# Project.net
KiCad netlist of a schematic drawn in EasyEDA Pro
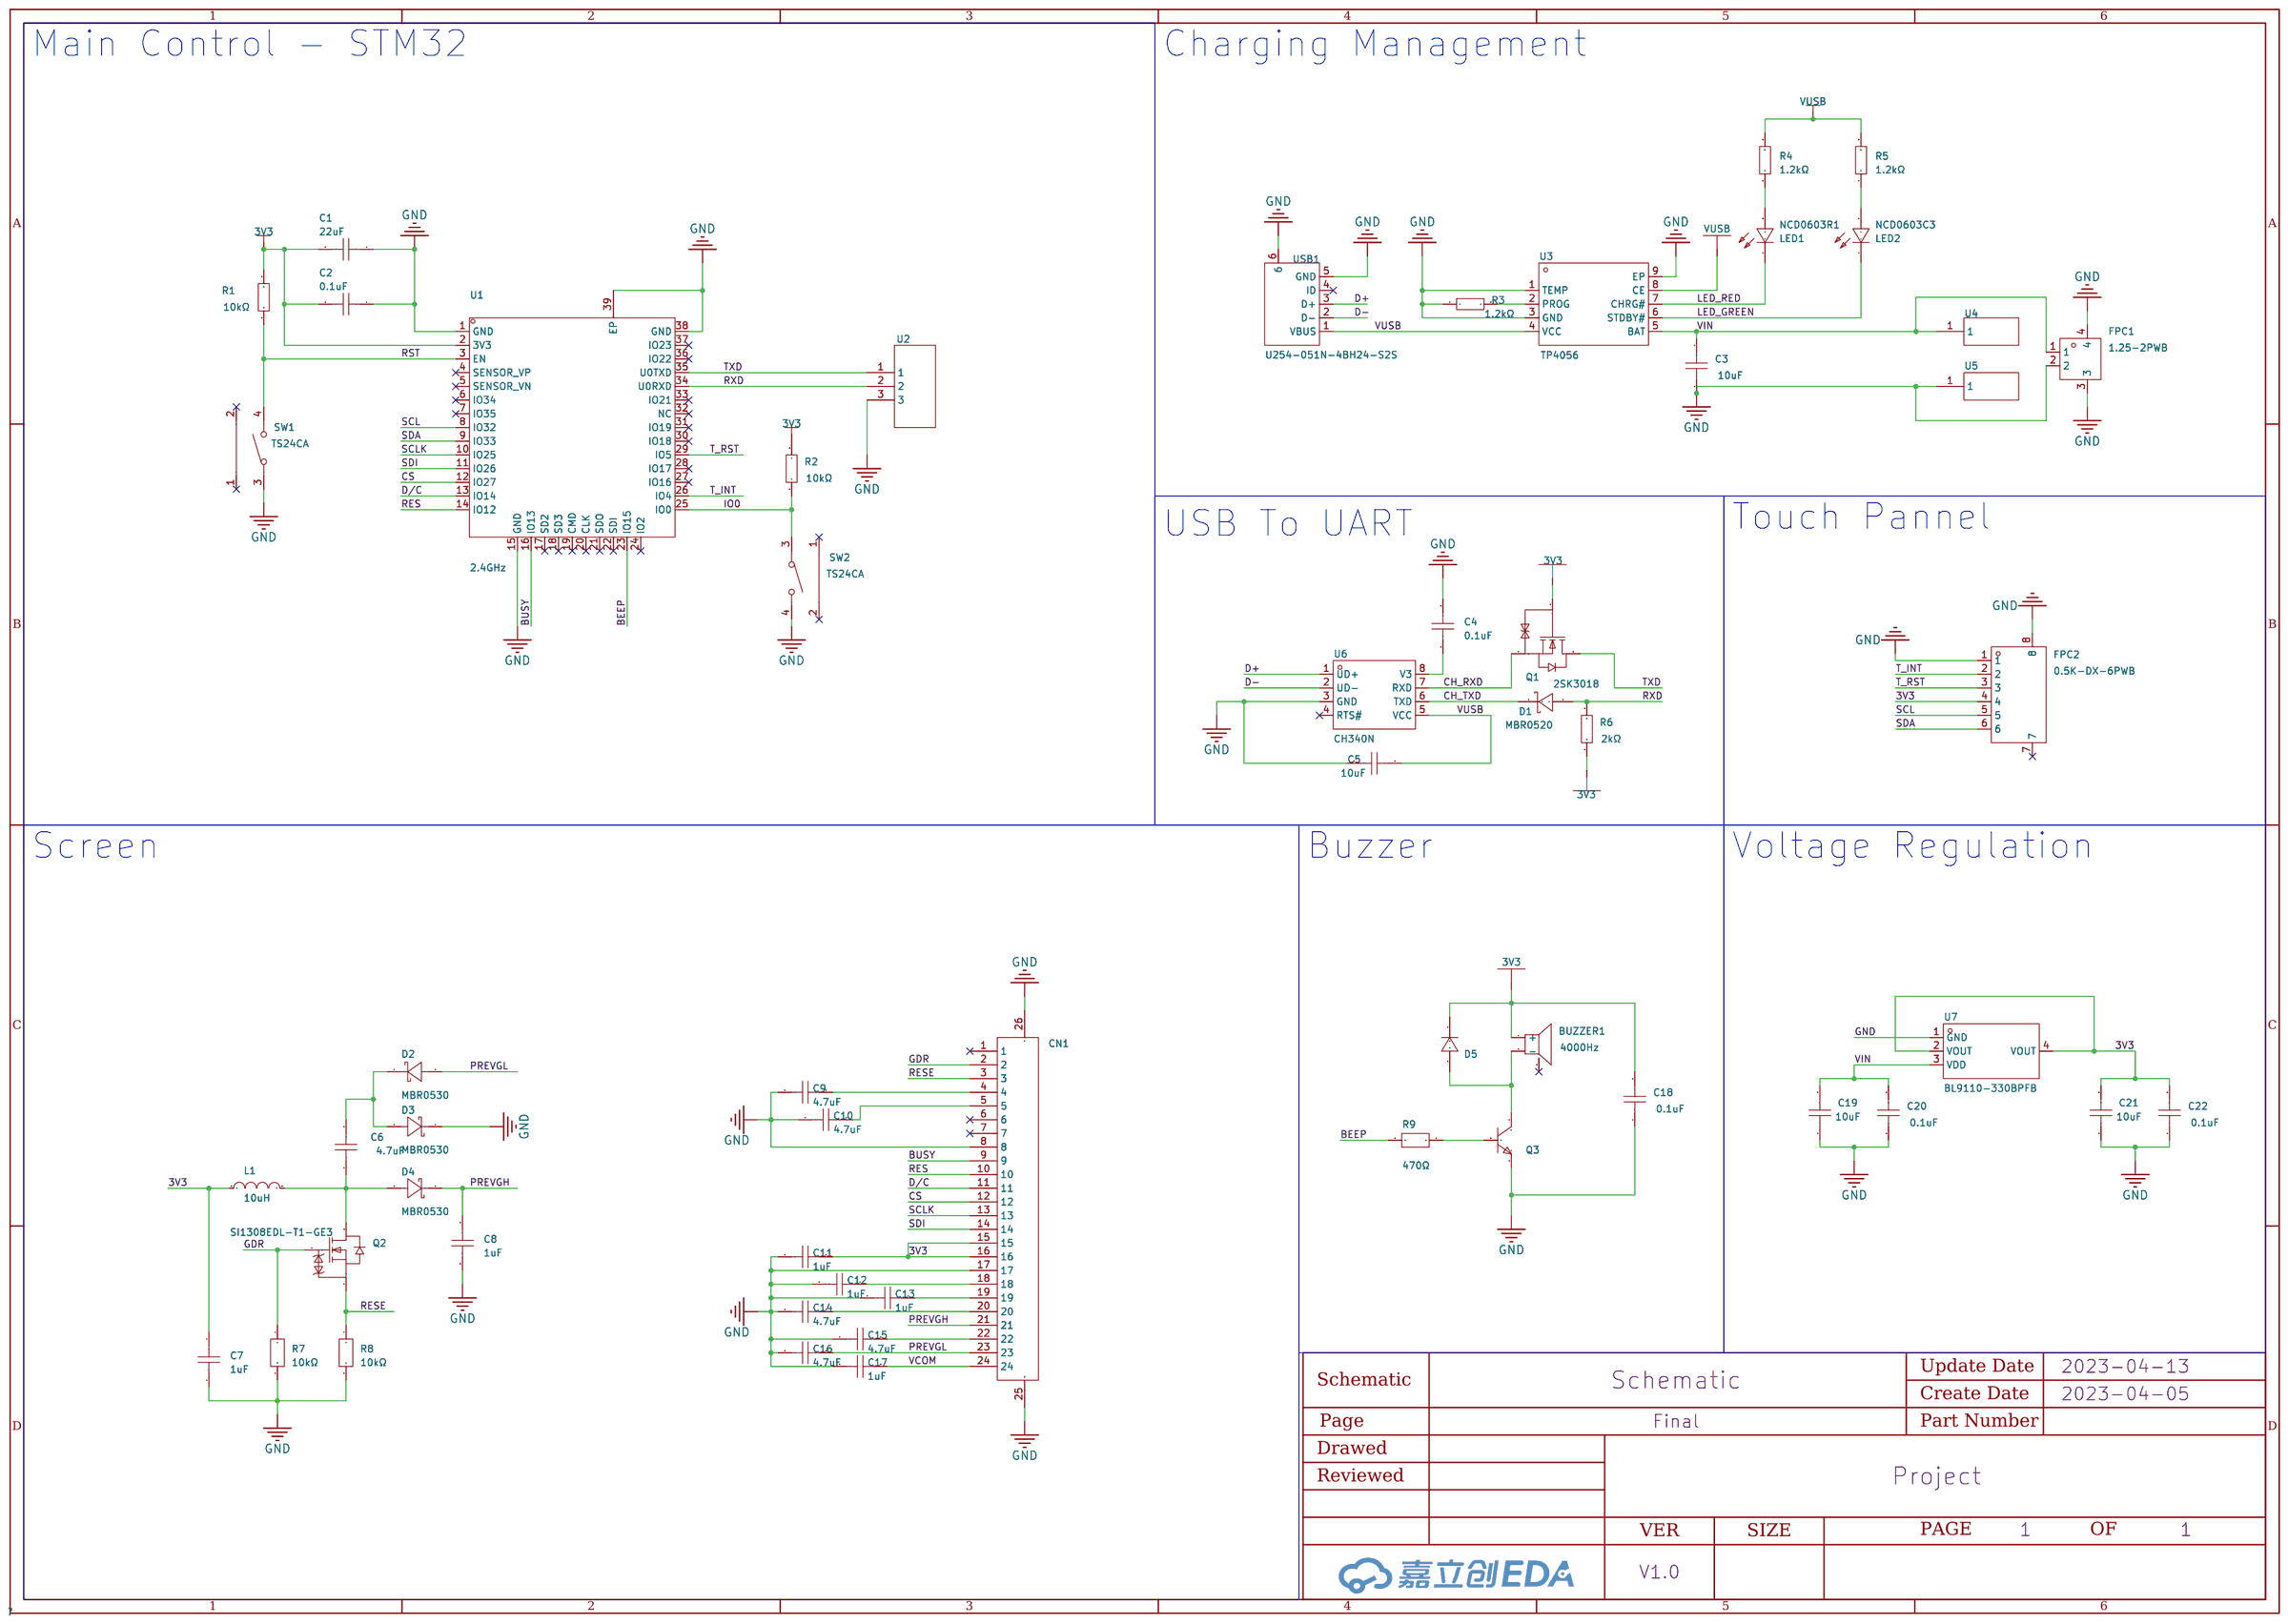
[diagram p0: schematic sheet]

(export (version "E")
  (design (tool "Eeschema 10.0.6"))
  (components
    (comp (ref "BUZZER1")
      (value "4000Hz")
      (footprint "easyedapro:BUZ-SMD_L5.0-W5.5-P4.60")
      (description "驱动方式:无源(外部驱动);构造类型:电磁式;频率:4000Hz;长度:5.2mm;宽度:5.2mm;高度:2.5mm;")
      (fields (field (name "Manufacturer Part") "MLT-5020") (field (name "Manufacturer") "华能"))
      (libsource (lib "easyedapro") (part "MLT-5020"))
    )
    (comp (ref "C1")
      (value "22uF")
      (footprint "easyedapro:c0603")
      (description "容值:22uF;精度:±0.25pF;额定电压:50V;温度系数:NP0;")
      (fields (field (name "Manufacturer Part") "MT18N1R5C500CT") (field (name "Manufacturer") "华新科(Walsin)"))
      (libsource (lib "easyedapro") (part "mt18n1r5c500ct"))
    )
    (comp (ref "C2")
      (value "0.1uF")
      (footprint "easyedapro:c0603")
      (description "容值：100nF 精度：±10% 额定电压：50V 材质(温度系数)：X7R 材质:X7R")
      (fields (field (name "Manufacturer Part") "MT18N1R5C500CT") (field (name "Manufacturer") "华新科(Walsin)"))
      (libsource (lib "easyedapro") (part "mt18n1r5c500ct"))
    )
    (comp (ref "C3")
      (value "10uF")
      (footprint "easyedapro:C0603")
      (description "容值:10uF;精度:±20%;额定电压:-;材质(温度系数):-;")
      (fields
        (field (name "Manufacturer Part") "JMK107BC6106MA-T")
        (field (name "Manufacturer") "TAIYO YUDEN(太诱)")
      )
      (libsource (lib "easyedapro") (part "JMK107BC6106MA-T"))
    )
    (comp (ref "C4")
      (value "0.1uF")
      (footprint "easyedapro:C0603")
      (description "温度系数:X7R;容值:100nF;电容体长:-;精度:±10%;电容体宽:-;电容体厚度:-;额定电压:50V;")
      (fields
        (field (name "Manufacturer Part") "CC0603KRX7R9BB104")
        (field (name "Manufacturer") "YAGEO(国巨)")
      )
      (libsource (lib "easyedapro") (part "CC0603KRX7R9BB104"))
    )
    (comp (ref "C5")
      (value "10uF")
      (footprint "easyedapro:c0603")
      (description "容值:10uF;精度:±0.25pF;额定电压:50V;温度系数:NP0;")
      (fields (field (name "Manufacturer Part") "MT18N1R5C500CT") (field (name "Manufacturer") "华新科(Walsin)"))
      (libsource (lib "easyedapro") (part "mt18n1r5c500ct"))
    )
    (comp (ref "C6")
      (value "4.7uF")
      (footprint "easyedapro:c0603")
      (description "容值：4.7uF 精度：±10% 额定电压：35V 材质(温度系数)：X5R")
      (fields (field (name "Manufacturer Part") "MT18N1R5C500CT") (field (name "Manufacturer") "华新科(Walsin)"))
      (libsource (lib "easyedapro") (part "mt18n1r5c500ct"))
    )
    (comp (ref "C7")
      (value "1uF")
      (footprint "easyedapro:c0603")
      (description "容值：1uF 精度：±10% 额定电压：50V 材质(温度系数)：X5R 材质:X5R")
      (fields (field (name "Manufacturer Part") "MT18N1R5C500CT") (field (name "Manufacturer") "华新科(Walsin)"))
      (libsource (lib "easyedapro") (part "mt18n1r5c500ct"))
    )
    (comp (ref "C8")
      (value "1uF")
      (footprint "easyedapro:c0603")
      (description "容值：1uF 精度：±10% 额定电压：50V 材质(温度系数)：X5R 材质:X5R")
      (fields (field (name "Manufacturer Part") "MT18N1R5C500CT") (field (name "Manufacturer") "华新科(Walsin)"))
      (libsource (lib "easyedapro") (part "mt18n1r5c500ct"))
    )
    (comp (ref "C9")
      (value "4.7uF")
      (footprint "easyedapro:C0603")
      (description "容值:4.7uF;精度:±10%;额定电压:35V;材质(温度系数):X5R;")
      (fields (field (name "Manufacturer Part") "C1608X5R1V475KT000E") (field (name "Manufacturer") "TDK"))
      (libsource (lib "easyedapro") (part "C1608X5R1V475KT000E"))
    )
    (comp (ref "C10")
      (value "4.7uF")
      (footprint "easyedapro:C0603")
      (description "容值:4.7uF;精度:±10%;额定电压:35V;材质(温度系数):X5R;")
      (fields (field (name "Manufacturer Part") "C1608X5R1V475KT000E") (field (name "Manufacturer") "TDK"))
      (libsource (lib "easyedapro") (part "C1608X5R1V475KT000E"))
    )
    (comp (ref "C11")
      (value "1uF")
      (footprint "easyedapro:c0603")
      (description "容值：1uF 精度：±10% 额定电压：50V 材质(温度系数)：X5R 材质:X5R")
      (fields (field (name "Manufacturer Part") "MT18N1R5C500CT") (field (name "Manufacturer") "华新科(Walsin)"))
      (libsource (lib "easyedapro") (part "mt18n1r5c500ct"))
    )
    (comp (ref "C12")
      (value "1uF")
      (footprint "easyedapro:c0603")
      (description "容值：1uF 精度：±10% 额定电压：50V 材质(温度系数)：X5R 材质:X5R")
      (fields (field (name "Manufacturer Part") "MT18N1R5C500CT") (field (name "Manufacturer") "华新科(Walsin)"))
      (libsource (lib "easyedapro") (part "mt18n1r5c500ct"))
    )
    (comp (ref "C13")
      (value "1uF")
      (footprint "easyedapro:c0603")
      (description "容值：1uF 精度：±10% 额定电压：50V 材质(温度系数)：X5R 材质:X5R")
      (fields (field (name "Manufacturer Part") "MT18N1R5C500CT") (field (name "Manufacturer") "华新科(Walsin)"))
      (libsource (lib "easyedapro") (part "mt18n1r5c500ct"))
    )
    (comp (ref "C14")
      (value "4.7uF")
      (footprint "easyedapro:C0603")
      (description "容值:4.7uF;精度:±10%;额定电压:35V;材质(温度系数):X5R;")
      (fields (field (name "Manufacturer Part") "C1608X5R1V475KT000E") (field (name "Manufacturer") "TDK"))
      (libsource (lib "easyedapro") (part "C1608X5R1V475KT000E"))
    )
    (comp (ref "C15")
      (value "4.7uF")
      (footprint "easyedapro:C0603")
      (description "容值:4.7uF;精度:±10%;额定电压:35V;材质(温度系数):X5R;")
      (fields (field (name "Manufacturer Part") "C1608X5R1V475KT000E") (field (name "Manufacturer") "TDK"))
      (libsource (lib "easyedapro") (part "C1608X5R1V475KT000E"))
    )
    (comp (ref "C16")
      (value "4.7uF")
      (footprint "easyedapro:C0603")
      (description "容值:4.7uF;精度:±10%;额定电压:35V;材质(温度系数):X5R;")
      (fields (field (name "Manufacturer Part") "C1608X5R1V475KT000E") (field (name "Manufacturer") "TDK"))
      (libsource (lib "easyedapro") (part "C1608X5R1V475KT000E"))
    )
    (comp (ref "C17")
      (value "1uF")
      (footprint "easyedapro:c0603")
      (description "容值：1uF 精度：±10% 额定电压：50V 材质(温度系数)：X5R 材质:X5R")
      (fields (field (name "Manufacturer Part") "MT18N1R5C500CT") (field (name "Manufacturer") "华新科(Walsin)"))
      (libsource (lib "easyedapro") (part "mt18n1r5c500ct"))
    )
    (comp (ref "C18")
      (value "0.1uF")
      (footprint "easyedapro:C0603")
      (description "容值:100nF;精度:±10%;额定电压:50V;温度系数:X7R;")
      (fields
        (field (name "Manufacturer Part") "CL10B104KB8NNNC")
        (field (name "Manufacturer") "SAMSUNG(三星)")
      )
      (libsource (lib "easyedapro") (part "CL10B104KB8NNNC"))
    )
    (comp (ref "C19")
      (value "10uF")
      (footprint "easyedapro:c0603")
      (description "容值:10uF;精度:±0.25pF;额定电压:50V;温度系数:NP0;")
      (fields (field (name "Manufacturer Part") "MT18N1R5C500CT") (field (name "Manufacturer") "华新科(Walsin)"))
      (libsource (lib "easyedapro") (part "mt18n1r5c500ct"))
    )
    (comp (ref "C20")
      (value "0.1uF")
      (footprint "easyedapro:C0603")
      (description "容值:100nF;精度:±10%;额定电压:50V;温度系数:X7R;")
      (fields
        (field (name "Manufacturer Part") "CL10B104KB8NNNC")
        (field (name "Manufacturer") "SAMSUNG(三星)")
      )
      (libsource (lib "easyedapro") (part "CL10B104KB8NNNC"))
    )
    (comp (ref "C21")
      (value "10uF")
      (footprint "easyedapro:c0603")
      (description "容值:10uF;精度:±0.25pF;额定电压:50V;温度系数:NP0;")
      (fields (field (name "Manufacturer Part") "MT18N1R5C500CT") (field (name "Manufacturer") "华新科(Walsin)"))
      (libsource (lib "easyedapro") (part "mt18n1r5c500ct"))
    )
    (comp (ref "C22")
      (value "0.1uF")
      (footprint "easyedapro:C0603")
      (description "容值:100nF;精度:±10%;额定电压:50V;温度系数:X7R;")
      (fields
        (field (name "Manufacturer Part") "CL10B104KB8NNNC")
        (field (name "Manufacturer") "SAMSUNG(三星)")
      )
      (libsource (lib "easyedapro") (part "CL10B104KB8NNNC"))
    )
    (comp (ref "CN1")
      (value "0.5-24P翻盖")
      (footprint "easyedapro:FPC-SMD_24P-P0.50-L6.1-W16.4")
      (description "间距:0.5mm;触点数量:24;锁定特性:翻盖式;安装类型:卧贴;触点类型:下接;工作温度范围:-;")
      (fields (field (name "Manufacturer") "BOOMELE(博穆精密)"))
      (libsource (lib "easyedapro") (part "FPC-Pitch0.5-24P-Bottom-Contact-Flip-Lock"))
    )
    (comp (ref "D1")
      (value "MBR0520")
      (footprint "easyedapro:SOD-123_L2.8-W1.8-LS3.7-RD")
      (description "直流反向耐压(Vr):20V;平均整流电流(Io):500mA;正向压降(Vf):450mV 500mA;")
      (fields (field (name "Manufacturer") "CJ（江苏长电/长晶）"))
      (libsource (lib "easyedapro") (part "MBR0520"))
    )
    (comp (ref "D2")
      (value "MBR0530")
      (footprint "easyedapro:SOD-123_L2.7-W1.6-LS3.7-RD-1")
      (fields (field (name "Manufacturer") "YANGJIE(扬杰)"))
      (libsource (lib "easyedapro") (part "MBR0530_C699108"))
    )
    (comp (ref "D3")
      (value "MBR0530")
      (footprint "easyedapro:SOD-123_L2.7-W1.6-LS3.7-RD-1")
      (fields (field (name "Manufacturer") "YANGJIE(扬杰)"))
      (libsource (lib "easyedapro") (part "MBR0530_C699108"))
    )
    (comp (ref "D4")
      (value "MBR0530")
      (footprint "easyedapro:SOD-123_L2.7-W1.6-LS3.7-RD-1")
      (fields (field (name "Manufacturer") "YANGJIE(扬杰)"))
      (libsource (lib "easyedapro") (part "MBR0530_C699108"))
    )
    (comp (ref "D5")
      (value "IN4148WS")
      (footprint "easyedapro:SOD-323_L1.8-W1.3-LS2.5-RD")
      (fields (field (name "Manufacturer") "LRC(乐山无线电)"))
      (libsource (lib "easyedapro") (part "IN4148WS"))
    )
    (comp (ref "FPC1")
      (value "1.25-2PWB")
      (footprint "easyedapro:CONN-SMD_2P-P1.25_DEALON_1.25-2PWB")
      (description "参考系列:-;间距:1.25mm;插针结构:1x2P;排数:1;每排PIN数:2;行距:-;公母:公型插针;安装方式:卧贴;额定电流:-;工作温度范围:-40~+85;")
      (fields (field (name "Manufacturer") "DEALON(德艺隆)"))
      (libsource (lib "easyedapro") (part "1.25-2PWB"))
    )
    (comp (ref "FPC2")
      (value "0.5K-DX-6PWB")
      (footprint "easyedapro:FPC-SMD_6P-P0.50_DEALON_0.5K-DX-6PWB")
      (description "间距:0.5mm;触点数量:6;锁定特性:翻盖式;安装类型:卧贴;触点类型:下接;工作温度范围:-20°C~+85°C;")
      (fields (field (name "Manufacturer") "HDGC(华德共创)"))
      (libsource (lib "easyedapro") (part "0.5K-DX-6PWB"))
    )
    (comp (ref "L1")
      (value "10uH")
      (footprint "easyedapro:ind-smd_l2.0-w1.6")
      (description "电感值:10uH;精度:±20%;额定电流:650mA;直流电阻(DCR):826mΩ;")
      (fields
        (field (name "Manufacturer Part") "WPN201610H100MT")
        (field (name "Manufacturer") "Sunlord(顺络)")
      )
      (libsource (lib "easyedapro") (part "wpn201610h100mt"))
    )
    (comp (ref "LED1")
      (value "NCD0603R1")
      (footprint "easyedapro:LED0603-RD_RED")
      (description "发光颜色:红灯;")
      (fields (field (name "Manufacturer") "国星光电"))
      (libsource (lib "easyedapro") (part "FC-DA1608HRK-620D"))
    )
    (comp (ref "LED2")
      (value "NCD0603C3")
      (footprint "easyedapro:LED0603-RD")
      (description "发光颜色:普绿/黄绿;")
      (fields (field (name "Manufacturer") "国星光电"))
      (libsource (lib "easyedapro") (part "FC-1608GEK-572E"))
    )
    (comp (ref "Q1")
      (value "2SK3018")
      (footprint "easyedapro:SOT-23-3_L2.9-W1.3-P1.90-LS2.4-BR")
      (fields (field (name "Manufacturer") "CJ（江苏长电/长晶）"))
      (libsource (lib "easyedapro") (part "2SK3018"))
    )
    (comp (ref "Q2")
      (value "SI1308EDL-T1-GE3")
      (footprint "easyedapro:SOT-323_L2.0-W1.3-P1.30-LS2.1-BR")
      (fields (field (name "Manufacturer") "VISHAY(威世)"))
      (libsource (lib "easyedapro") (part "SI1308EDL-T1-GE3"))
    )
    (comp (ref "Q3")
      (value "KST8050S")
      (footprint "easyedapro:SOT-23_L2.9-W1.3-P1.90-LS2.4-BR")
      (description "晶体管类型:NPN;集射极击穿电压(Vceo):25V;集电极电流(Ic):500mA;功率(Pd):300mW;")
      (fields (field (name "Manufacturer") "KEXIN(科信)"))
      (libsource (lib "easyedapro") (part "KST8050S"))
    )
    (comp (ref "R1")
      (value "10kΩ")
      (footprint "easyedapro:R0603")
      (description "电阻类型:厚膜电阻;阻值:10kΩ;精度:±0.1%;功率:200mW;温度系数:±50ppm/℃;最大工作电压:200V;工作温度范围:-55℃~+155℃;")
      (fields (field (name "Manufacturer Part") "ERJPB3B1002V") (field (name "Manufacturer") "PANASONIC(松下)"))
      (libsource (lib "easyedapro") (part "ERJPB3B1002V"))
    )
    (comp (ref "R2")
      (value "10kΩ")
      (footprint "easyedapro:R0603")
      (description "电阻类型:厚膜电阻;阻值:10kΩ;精度:±0.1%;功率:200mW;温度系数:±50ppm/°C;最大工作电压:200V;工作温度范围:-55°C~+155°C;")
      (fields (field (name "Manufacturer Part") "ERJPB3B1002V") (field (name "Manufacturer") "PANASONIC(松下)"))
      (libsource (lib "easyedapro") (part "ERJPB3B1002V"))
    )
    (comp (ref "R3")
      (value "1.2kΩ")
      (footprint "easyedapro:R0603")
      (description "电阻类型:厚膜电阻;阻值:1.2kΩ;精度:±5%;功率:100mW;温度系数:±200ppm/°C;最大工作电压:50V;工作温度范围:-55°C~+155°C;")
      (fields (field (name "Manufacturer Part") "MCR03EZPJ122") (field (name "Manufacturer") "ROHM(罗姆)"))
      (libsource (lib "easyedapro") (part "MCR03EZPJ122"))
    )
    (comp (ref "R4")
      (value "1.2kΩ")
      (footprint "easyedapro:R0603")
      (description "电阻类型:厚膜电阻;阻值:1.2kΩ;精度:±5%;功率:100mW;温度系数:±200ppm/℃;最大工作电压:50V;工作温度范围:-55℃~+155℃;")
      (fields (field (name "Manufacturer Part") "MCR03EZPJ122") (field (name "Manufacturer") "ROHM(罗姆)"))
      (libsource (lib "easyedapro") (part "MCR03EZPJ122"))
    )
    (comp (ref "R5")
      (value "1.2kΩ")
      (footprint "easyedapro:R0603")
      (description "电阻类型:厚膜电阻;阻值:1.2kΩ;精度:±5%;功率:100mW;温度系数:±200ppm/℃;最大工作电压:50V;工作温度范围:-55℃~+155℃;")
      (fields (field (name "Manufacturer Part") "MCR03EZPJ122") (field (name "Manufacturer") "ROHM(罗姆)"))
      (libsource (lib "easyedapro") (part "MCR03EZPJ122"))
    )
    (comp (ref "R6")
      (value "2kΩ")
      (footprint "easyedapro:R0603")
      (description "精度:±1%;阻值:2kΩ;温度系数:±100ppm/℃;功率:1/10W;最大工作电压:75V;工作温度范围:-55℃~+155℃;")
      (fields
        (field (name "Manufacturer Part") "0603WAF2001T5E")
        (field (name "Manufacturer") "UNI-ROYAL(厚声)")
      )
      (libsource (lib "easyedapro") (part "0603WAF2001T5E"))
    )
    (comp (ref "R7")
      (value "10kΩ")
      (footprint "easyedapro:r0603")
      (description "阻值:10kΩ;精度:±1%;功率:-;温度系数:-;")
      (fields (field (name "Manufacturer Part") "SG73P1JTTD1002F") (field (name "Manufacturer") "KOA"))
      (libsource (lib "easyedapro") (part "sg73p1jttd1002f"))
    )
    (comp (ref "R8")
      (value "10kΩ")
      (footprint "easyedapro:r0603")
      (description "阻值:10kΩ;精度:±1%;功率:-;温度系数:-;")
      (fields (field (name "Manufacturer Part") "SG73P1JTTD1002F") (field (name "Manufacturer") "KOA"))
      (libsource (lib "easyedapro") (part "sg73p1jttd1002f"))
    )
    (comp (ref "R9")
      (value "470Ω")
      (footprint "easyedapro:r0603")
      (description "阻值:470Ω;精度:±1%;功率:-;温度系数:-;")
      (fields (field (name "Manufacturer Part") "SG73P1JTTD1002F") (field (name "Manufacturer") "KOA"))
      (libsource (lib "easyedapro") (part "sg73p1jttd1002f"))
    )
    (comp (ref "SW1")
      (value "TS24CA")
      (footprint "easyedapro:SW-SMD_TS24CA")
      (description "触点电流:50mA;额定电压(DC):12V;电路结构:单刀单掷;安装方式:卧贴;按钮形状:矩形按钮;带灯:-;开关长度:4.55mm;开关宽度:1.8mm;开关高度:3.5mm;")
      (fields (field (name "Manufacturer") "SHOU HAN(首韩)"))
      (libsource (lib "easyedapro") (part "TS24CA"))
    )
    (comp (ref "SW2")
      (value "TS24CA")
      (footprint "easyedapro:SW-SMD_TS24CA")
      (description "触点电流:50mA;额定电压(DC):12V;电路结构:单刀单掷;安装方式:卧贴;按钮形状:矩形按钮;带灯:-;开关长度:4.55mm;开关宽度:1.8mm;开关高度:3.5mm;")
      (fields (field (name "Manufacturer") "SHOU HAN(首韩)"))
      (libsource (lib "easyedapro") (part "TS24CA"))
    )
    (comp (ref "U1")
      (value "2.4GHz")
      (footprint "easyedapro:WIRELM-SMD_ESP32-S")
      (description "频率:2.4GHz;发射功率:17dBm;核心处理器:LX6;天线形式:板载 PCB 天线/外接 IPEX;接收灵敏度:-90dBm;")
      (fields (field (name "Manufacturer Part") "ESP32-S") (field (name "Manufacturer") "Ai-Thinker(安信可)"))
      (libsource (lib "easyedapro") (part "ESP32-S"))
    )
    (comp (ref "U2") (value "~") (footprint "easyedapro:下载调试点") (libsource (lib "easyedapro") (part "下载调试点")))
    (comp (ref "U3")
      (value "TP4056")
      (footprint "easyedapro:ESOP-8_L4.9-W3.9-P1.27-LS6.0-BL-EP")
      (fields (field (name "Manufacturer") "TPOWER(天源)"))
      (libsource (lib "easyedapro") (part "TP4056_C382139"))
    )
    (comp (ref "U4")
      (value "~")
      (footprint "easyedapro:电池焊接端子封装2")
      (libsource (lib "easyedapro") (part "电池焊接端子2"))
    )
    (comp (ref "U5")
      (value "~")
      (footprint "easyedapro:电池焊接端子封装2")
      (libsource (lib "easyedapro") (part "电池焊接端子2"))
    )
    (comp (ref "U6")
      (value "CH340N")
      (footprint "easyedapro:SOP-8_L4.9-W3.9-P1.27-LS6.0-BL")
      (fields (field (name "Manufacturer") "WCH(南京沁恒)"))
      (libsource (lib "easyedapro") (part "CH340N_C2977777"))
    )
    (comp (ref "U7")
      (value "BL9110-330BPFB")
      (footprint "easyedapro:SOT-223_L6.5-W3.5-P2.30-LS7.0-BR")
      (description "输出类型:固定;输出极性:正;输出通道数:1;最大输入电压:6V;输出电压:3.3V;压差:390mV@(1A);输出电流:1A;电源纹波抑制比(PRSS):70dB@(1kHz);")
      (fields (field (name "Manufacturer") "BL(上海贝岭)"))
      (libsource (lib "easyedapro") (part "BL9110-330BPFB"))
    )
    (comp (ref "USB1")
      (value "U254-051N-4BH24-S2S")
      (footprint "easyedapro:MICRO-USB-SMD_U254-051N-4BH24-S2")
      (fields (field (name "Manufacturer") "XKB Connectivity(中国星坤)"))
      (libsource (lib "easyedapro") (part "U254-051N-4BH24-S2S"))
    )
  )
  (nets
    (net (code "1") (name "/BEEP") (class "Default")
      (node (ref "R9") (pin "1") (pinfunction "1_1") (pintype "input"))
      (node (ref "U1") (pin "23") (pinfunction "IO15_23") (pintype "input"))
    )
    (net (code "2") (name "/BUSY") (class "Default")
      (node (ref "CN1") (pin "9") (pinfunction "9_9") (pintype "input"))
      (node (ref "U1") (pin "16") (pinfunction "IO13_16") (pintype "input"))
    )
    (net (code "3") (name "/CH_RXD") (class "Default")
      (node (ref "Q1") (pin "2") (pinfunction "S_2") (pintype "input"))
      (node (ref "U6") (pin "7") (pinfunction "RXD_7") (pintype "input"))
    )
    (net (code "4") (name "/CH_TXD") (class "Default")
      (node (ref "D1") (pin "1") (pinfunction "K_1") (pintype "input"))
      (node (ref "U6") (pin "6") (pinfunction "TXD_6") (pintype "input"))
    )
    (net (code "5") (name "/CS") (class "Default")
      (node (ref "CN1") (pin "12") (pinfunction "12_12") (pintype "input"))
      (node (ref "U1") (pin "12") (pinfunction "IO27_12") (pintype "input"))
    )
    (net (code "6") (name "/D+") (class "Default")
      (node (ref "U6") (pin "1") (pinfunction "UD+_1") (pintype "input"))
      (node (ref "USB1") (pin "3") (pinfunction "D+_3") (pintype "input"))
    )
    (net (code "7") (name "/D-") (class "Default")
      (node (ref "U6") (pin "2") (pinfunction "UD-_2") (pintype "input"))
      (node (ref "USB1") (pin "2") (pinfunction "D-_2") (pintype "input"))
    )
    (net (code "8") (name "/D{slash}C") (class "Default")
      (node (ref "CN1") (pin "11") (pinfunction "11_11") (pintype "input"))
      (node (ref "U1") (pin "13") (pinfunction "IO14_13") (pintype "input"))
    )
    (net (code "9") (name "/GDR") (class "Default")
      (node (ref "CN1") (pin "2") (pinfunction "2_2") (pintype "input"))
      (node (ref "Q2") (pin "1") (pinfunction "G_1") (pintype "input"))
      (node (ref "R7") (pin "1") (pinfunction "1_1") (pintype "input"))
    )
    (net (code "10") (name "/IO0") (class "Default")
      (node (ref "R2") (pin "1") (pinfunction "1_1") (pintype "input"))
      (node (ref "SW2") (pin "3") (pinfunction "3_3") (pintype "input"))
      (node (ref "U1") (pin "25") (pinfunction "IO0_25") (pintype "input"))
    )
    (net (code "11") (name "/LED_GREEN") (class "Default")
      (node (ref "LED2") (pin "1") (pinfunction "K_1") (pintype "input"))
      (node (ref "U3") (pin "6") (pinfunction "STDBY#_6") (pintype "input"))
    )
    (net (code "12") (name "/LED_RED") (class "Default")
      (node (ref "LED1") (pin "1") (pinfunction "K_1") (pintype "input"))
      (node (ref "U3") (pin "7") (pinfunction "CHRG#_7") (pintype "input"))
    )
    (net (code "13") (name "/PREVGH") (class "Default")
      (node (ref "C8") (pin "1") (pinfunction "1_1") (pintype "input"))
      (node (ref "CN1") (pin "21") (pinfunction "21_21") (pintype "input"))
      (node (ref "D4") (pin "1") (pinfunction "K_1") (pintype "input"))
    )
    (net (code "14") (name "/PREVGL") (class "Default")
      (node (ref "C16") (pin "2") (pinfunction "2_2") (pintype "input"))
      (node (ref "CN1") (pin "23") (pinfunction "23_23") (pintype "input"))
      (node (ref "D2") (pin "2") (pinfunction "A_2") (pintype "input"))
    )
    (net (code "15") (name "/RES") (class "Default")
      (node (ref "CN1") (pin "10") (pinfunction "10_10") (pintype "input"))
      (node (ref "U1") (pin "14") (pinfunction "IO12_14") (pintype "input"))
    )
    (net (code "16") (name "/RESE") (class "Default")
      (node (ref "CN1") (pin "3") (pinfunction "3_3") (pintype "input"))
      (node (ref "Q2") (pin "2") (pinfunction "S_2") (pintype "input"))
      (node (ref "R8") (pin "1") (pinfunction "1_1") (pintype "input"))
    )
    (net (code "17") (name "/RST") (class "Default")
      (node (ref "R1") (pin "1") (pinfunction "1_1") (pintype "input"))
      (node (ref "SW1") (pin "4") (pinfunction "4_4") (pintype "input"))
      (node (ref "U1") (pin "3") (pinfunction "EN_3") (pintype "input"))
    )
    (net (code "18") (name "/RXD") (class "Default")
      (node (ref "D1") (pin "2") (pinfunction "A_2") (pintype "input"))
      (node (ref "R6") (pin "2") (pinfunction "2_2") (pintype "input"))
      (node (ref "U1") (pin "34") (pinfunction "U0RXD_34") (pintype "input"))
      (node (ref "U2") (pin "2") (pinfunction "2_2") (pintype "input"))
    )
    (net (code "19") (name "/SCL") (class "Default")
      (node (ref "FPC2") (pin "5") (pinfunction "5_5") (pintype "input"))
      (node (ref "U1") (pin "8") (pinfunction "IO32_8") (pintype "input"))
    )
    (net (code "20") (name "/SCLK") (class "Default")
      (node (ref "CN1") (pin "13") (pinfunction "13_13") (pintype "input"))
      (node (ref "U1") (pin "10") (pinfunction "IO25_10") (pintype "input"))
    )
    (net (code "21") (name "/SDA") (class "Default")
      (node (ref "FPC2") (pin "6") (pinfunction "6_6") (pintype "input"))
      (node (ref "U1") (pin "9") (pinfunction "IO33_9") (pintype "input"))
    )
    (net (code "22") (name "/SDI") (class "Default")
      (node (ref "CN1") (pin "14") (pinfunction "14_14") (pintype "input"))
      (node (ref "U1") (pin "11") (pinfunction "IO26_11") (pintype "input"))
    )
    (net (code "23") (name "/TXD") (class "Default")
      (node (ref "Q1") (pin "3") (pinfunction "D_3") (pintype "input"))
      (node (ref "U1") (pin "35") (pinfunction "U0TXD_35") (pintype "input"))
      (node (ref "U2") (pin "1") (pinfunction "1_1") (pintype "input"))
    )
    (net (code "24") (name "/T_INT") (class "Default")
      (node (ref "FPC2") (pin "2") (pinfunction "2_2") (pintype "input"))
      (node (ref "U1") (pin "26") (pinfunction "IO4_26") (pintype "input"))
    )
    (net (code "25") (name "/T_RST") (class "Default")
      (node (ref "FPC2") (pin "3") (pinfunction "3_3") (pintype "input"))
      (node (ref "U1") (pin "29") (pinfunction "IO5_29") (pintype "input"))
    )
    (net (code "26") (name "/VCOM") (class "Default")
      (node (ref "C17") (pin "1") (pinfunction "1_1") (pintype "input"))
      (node (ref "CN1") (pin "24") (pinfunction "24_24") (pintype "input"))
    )
    (net (code "27") (name "/VIN") (class "Default")
      (node (ref "C19") (pin "2") (pinfunction "2_2") (pintype "input"))
      (node (ref "C20") (pin "2") (pinfunction "2_2") (pintype "input"))
      (node (ref "C3") (pin "2") (pinfunction "2_2") (pintype "input"))
      (node (ref "FPC1") (pin "1") (pinfunction "1_1") (pintype "input"))
      (node (ref "U3") (pin "5") (pinfunction "BAT_5") (pintype "input"))
      (node (ref "U4") (pin "1") (pinfunction "1_1") (pintype "input"))
      (node (ref "U7") (pin "3") (pinfunction "VDD_3") (pintype "input"))
    )
    (net (code "28") (name "3V3") (class "Default")
      (node (ref "BUZZER1") (pin "1") (pinfunction "+_1") (pintype "input"))
      (node (ref "C1") (pin "2") (pinfunction "2_2") (pintype "input"))
      (node (ref "C11") (pin "1") (pinfunction "1_1") (pintype "input"))
      (node (ref "C18") (pin "2") (pinfunction "2_2") (pintype "input"))
      (node (ref "C2") (pin "2") (pinfunction "2_2") (pintype "input"))
      (node (ref "C21") (pin "2") (pinfunction "2_2") (pintype "input"))
      (node (ref "C22") (pin "2") (pinfunction "2_2") (pintype "input"))
      (node (ref "C7") (pin "1") (pinfunction "1_1") (pintype "input"))
      (node (ref "CN1") (pin "15") (pinfunction "15_15") (pintype "input"))
      (node (ref "CN1") (pin "16") (pinfunction "16_16") (pintype "input"))
      (node (ref "D5") (pin "1") (pinfunction "C_1") (pintype "input"))
      (node (ref "FPC2") (pin "4") (pinfunction "4_4") (pintype "input"))
      (node (ref "L1") (pin "1") (pinfunction "1_1") (pintype "input"))
      (node (ref "Q1") (pin "1") (pinfunction "G_1") (pintype "input"))
      (node (ref "R1") (pin "2") (pinfunction "2_2") (pintype "input"))
      (node (ref "R2") (pin "2") (pinfunction "2_2") (pintype "input"))
      (node (ref "R6") (pin "1") (pinfunction "1_1") (pintype "input"))
      (node (ref "U1") (pin "2") (pinfunction "3V3_2") (pintype "input"))
      (node (ref "U7") (pin "2") (pinfunction "VOUT_2") (pintype "input"))
      (node (ref "U7") (pin "4") (pinfunction "VOUT_4") (pintype "input"))
    )
    (net (code "29") (name "GND") (class "Default")
      (node (ref "C1") (pin "1") (pinfunction "1_1") (pintype "input"))
      (node (ref "C10") (pin "1") (pinfunction "1_1") (pintype "input"))
      (node (ref "C11") (pin "2") (pinfunction "2_2") (pintype "input"))
      (node (ref "C12") (pin "2") (pinfunction "2_2") (pintype "input"))
      (node (ref "C13") (pin "2") (pinfunction "2_2") (pintype "input"))
      (node (ref "C14") (pin "1") (pinfunction "1_1") (pintype "input"))
      (node (ref "C15") (pin "1") (pinfunction "1_1") (pintype "input"))
      (node (ref "C16") (pin "1") (pinfunction "1_1") (pintype "input"))
      (node (ref "C17") (pin "2") (pinfunction "2_2") (pintype "input"))
      (node (ref "C18") (pin "1") (pinfunction "1_1") (pintype "input"))
      (node (ref "C19") (pin "1") (pinfunction "1_1") (pintype "input"))
      (node (ref "C2") (pin "1") (pinfunction "1_1") (pintype "input"))
      (node (ref "C20") (pin "1") (pinfunction "1_1") (pintype "input"))
      (node (ref "C21") (pin "1") (pinfunction "1_1") (pintype "input"))
      (node (ref "C22") (pin "1") (pinfunction "1_1") (pintype "input"))
      (node (ref "C3") (pin "1") (pinfunction "1_1") (pintype "input"))
      (node (ref "C4") (pin "2") (pinfunction "2_2") (pintype "input"))
      (node (ref "C5") (pin "2") (pinfunction "2_2") (pintype "input"))
      (node (ref "C7") (pin "2") (pinfunction "2_2") (pintype "input"))
      (node (ref "C8") (pin "2") (pinfunction "2_2") (pintype "input"))
      (node (ref "C9") (pin "1") (pinfunction "1_1") (pintype "input"))
      (node (ref "CN1") (pin "17") (pinfunction "17_17") (pintype "input"))
      (node (ref "CN1") (pin "25") (pinfunction "25_25") (pintype "input"))
      (node (ref "CN1") (pin "26") (pinfunction "26_26") (pintype "input"))
      (node (ref "CN1") (pin "8") (pinfunction "8_8") (pintype "input"))
      (node (ref "D3") (pin "1") (pinfunction "K_1") (pintype "input"))
      (node (ref "FPC1") (pin "2") (pinfunction "2_2") (pintype "input"))
      (node (ref "FPC1") (pin "3") (pinfunction "3_3") (pintype "input"))
      (node (ref "FPC1") (pin "4") (pinfunction "4_4") (pintype "input"))
      (node (ref "FPC2") (pin "1") (pinfunction "1_1") (pintype "input"))
      (node (ref "FPC2") (pin "8") (pinfunction "8_8") (pintype "input"))
      (node (ref "Q3") (pin "2") (pinfunction "E_2") (pintype "input"))
      (node (ref "R3") (pin "1") (pinfunction "1_1") (pintype "input"))
      (node (ref "R7") (pin "2") (pinfunction "2_2") (pintype "input"))
      (node (ref "R8") (pin "2") (pinfunction "2_2") (pintype "input"))
      (node (ref "SW1") (pin "3") (pinfunction "3_3") (pintype "input"))
      (node (ref "SW2") (pin "4") (pinfunction "4_4") (pintype "input"))
      (node (ref "U1") (pin "1") (pinfunction "GND_1") (pintype "input"))
      (node (ref "U1") (pin "15") (pinfunction "GND_15") (pintype "input"))
      (node (ref "U1") (pin "38") (pinfunction "GND_38") (pintype "input"))
      (node (ref "U1") (pin "39") (pinfunction "EP_39") (pintype "input"))
      (node (ref "U2") (pin "3") (pinfunction "3_3") (pintype "input"))
      (node (ref "U3") (pin "1") (pinfunction "TEMP_1") (pintype "input"))
      (node (ref "U3") (pin "3") (pinfunction "GND_3") (pintype "input"))
      (node (ref "U3") (pin "9") (pinfunction "EP_9") (pintype "input"))
      (node (ref "U5") (pin "1") (pinfunction "1_1") (pintype "input"))
      (node (ref "U6") (pin "3") (pinfunction "GND_3") (pintype "input"))
      (node (ref "U7") (pin "1") (pinfunction "GND_1") (pintype "input"))
      (node (ref "USB1") (pin "5") (pinfunction "GND_5") (pintype "input"))
      (node (ref "USB1") (pin "6") (pinfunction "6_6") (pintype "input"))
    )
    (net (code "30") (name "Net-(BUZZER1--)") (class "Default")
      (node (ref "BUZZER1") (pin "2") (pinfunction "-_2") (pintype "input"))
      (node (ref "D5") (pin "2") (pinfunction "A_2") (pintype "input"))
      (node (ref "Q3") (pin "3") (pinfunction "C_3") (pintype "input"))
    )
    (net (code "31") (name "Net-(C9-Pad2)") (class "Default")
      (node (ref "C9") (pin "2") (pinfunction "2_2") (pintype "input"))
      (node (ref "CN1") (pin "4") (pinfunction "4_4") (pintype "input"))
    )
    (net (code "32") (name "Net-(C10-Pad2)") (class "Default")
      (node (ref "C10") (pin "2") (pinfunction "2_2") (pintype "input"))
      (node (ref "CN1") (pin "5") (pinfunction "5_5") (pintype "input"))
    )
    (net (code "33") (name "Net-(C12-Pad1)") (class "Default")
      (node (ref "C12") (pin "1") (pinfunction "1_1") (pintype "input"))
      (node (ref "CN1") (pin "18") (pinfunction "18_18") (pintype "input"))
    )
    (net (code "34") (name "Net-(C13-Pad1)") (class "Default")
      (node (ref "C13") (pin "1") (pinfunction "1_1") (pintype "input"))
      (node (ref "CN1") (pin "19") (pinfunction "19_19") (pintype "input"))
    )
    (net (code "35") (name "Net-(C14-Pad2)") (class "Default")
      (node (ref "C14") (pin "2") (pinfunction "2_2") (pintype "input"))
      (node (ref "CN1") (pin "20") (pinfunction "20_20") (pintype "input"))
    )
    (net (code "36") (name "Net-(C15-Pad2)") (class "Default")
      (node (ref "C15") (pin "2") (pinfunction "2_2") (pintype "input"))
      (node (ref "CN1") (pin "22") (pinfunction "22_22") (pintype "input"))
    )
    (net (code "37") (name "Net-(D2-K)") (class "Default")
      (node (ref "C6") (pin "2") (pinfunction "2_2") (pintype "input"))
      (node (ref "D2") (pin "1") (pinfunction "K_1") (pintype "input"))
      (node (ref "D3") (pin "2") (pinfunction "A_2") (pintype "input"))
    )
    (net (code "38") (name "Net-(D4-A)") (class "Default")
      (node (ref "C6") (pin "1") (pinfunction "1_1") (pintype "input"))
      (node (ref "D4") (pin "2") (pinfunction "A_2") (pintype "input"))
      (node (ref "L1") (pin "2") (pinfunction "2_2") (pintype "input"))
      (node (ref "Q2") (pin "3") (pinfunction "D_3") (pintype "input"))
    )
    (net (code "39") (name "Net-(LED1-A)") (class "Default")
      (node (ref "LED1") (pin "2") (pinfunction "A_2") (pintype "input"))
      (node (ref "R4") (pin "1") (pinfunction "1_1") (pintype "input"))
    )
    (net (code "40") (name "Net-(LED2-A)") (class "Default")
      (node (ref "LED2") (pin "2") (pinfunction "A_2") (pintype "input"))
      (node (ref "R5") (pin "1") (pinfunction "1_1") (pintype "input"))
    )
    (net (code "41") (name "Net-(Q3-B)") (class "Default")
      (node (ref "Q3") (pin "1") (pinfunction "B_1") (pintype "input"))
      (node (ref "R9") (pin "2") (pinfunction "2_2") (pintype "input"))
    )
    (net (code "42") (name "Net-(U3-PROG)") (class "Default")
      (node (ref "R3") (pin "2") (pinfunction "2_2") (pintype "input"))
      (node (ref "U3") (pin "2") (pinfunction "PROG_2") (pintype "input"))
    )
    (net (code "43") (name "Net-(U6-V3)") (class "Default")
      (node (ref "C4") (pin "1") (pinfunction "1_1") (pintype "input"))
      (node (ref "U6") (pin "8") (pinfunction "V3_8") (pintype "input"))
    )
    (net (code "44") (name "VUSB") (class "Default")
      (node (ref "C5") (pin "1") (pinfunction "1_1") (pintype "input"))
      (node (ref "R4") (pin "2") (pinfunction "2_2") (pintype "input"))
      (node (ref "R5") (pin "2") (pinfunction "2_2") (pintype "input"))
      (node (ref "U3") (pin "4") (pinfunction "VCC_4") (pintype "input"))
      (node (ref "U3") (pin "8") (pinfunction "CE_8") (pintype "input"))
      (node (ref "U6") (pin "5") (pinfunction "VCC_5") (pintype "input"))
      (node (ref "USB1") (pin "1") (pinfunction "VBUS_1") (pintype "input"))
    )
    (net (code "45") (name "unconnected-(BUZZER1-NC-Pad3)") (class "Default")
      (node (ref "BUZZER1") (pin "3") (pinfunction "NC_3") (pintype "input+no_connect"))
    )
    (net (code "46") (name "unconnected-(CN1-Pad1)") (class "Default")
      (node (ref "CN1") (pin "1") (pinfunction "1_1") (pintype "input+no_connect"))
    )
    (net (code "47") (name "unconnected-(CN1-Pad6)") (class "Default")
      (node (ref "CN1") (pin "6") (pinfunction "6_6") (pintype "input+no_connect"))
    )
    (net (code "48") (name "unconnected-(CN1-Pad7)") (class "Default")
      (node (ref "CN1") (pin "7") (pinfunction "7_7") (pintype "input+no_connect"))
    )
    (net (code "49") (name "unconnected-(FPC2-Pad7)") (class "Default")
      (node (ref "FPC2") (pin "7") (pinfunction "7_7") (pintype "input+no_connect"))
    )
    (net (code "50") (name "unconnected-(SW1-Pad1)") (class "Default")
      (node (ref "SW1") (pin "1") (pinfunction "1_1") (pintype "input+no_connect"))
    )
    (net (code "51") (name "unconnected-(SW1-Pad2)") (class "Default")
      (node (ref "SW1") (pin "2") (pinfunction "2_2") (pintype "input+no_connect"))
    )
    (net (code "52") (name "unconnected-(SW2-Pad1)") (class "Default")
      (node (ref "SW2") (pin "1") (pinfunction "1_1") (pintype "input+no_connect"))
    )
    (net (code "53") (name "unconnected-(SW2-Pad2)") (class "Default")
      (node (ref "SW2") (pin "2") (pinfunction "2_2") (pintype "input+no_connect"))
    )
    (net (code "54") (name "unconnected-(U1-CLK-Pad20)") (class "Default")
      (node (ref "U1") (pin "20") (pinfunction "CLK_20") (pintype "input+no_connect"))
    )
    (net (code "55") (name "unconnected-(U1-CMD-Pad19)") (class "Default")
      (node (ref "U1") (pin "19") (pinfunction "CMD_19") (pintype "input+no_connect"))
    )
    (net (code "56") (name "unconnected-(U1-IO2-Pad24)") (class "Default")
      (node (ref "U1") (pin "24") (pinfunction "IO2_24") (pintype "input+no_connect"))
    )
    (net (code "57") (name "unconnected-(U1-IO16-Pad27)") (class "Default")
      (node (ref "U1") (pin "27") (pinfunction "IO16_27") (pintype "input+no_connect"))
    )
    (net (code "58") (name "unconnected-(U1-IO17-Pad28)") (class "Default")
      (node (ref "U1") (pin "28") (pinfunction "IO17_28") (pintype "input+no_connect"))
    )
    (net (code "59") (name "unconnected-(U1-IO18-Pad30)") (class "Default")
      (node (ref "U1") (pin "30") (pinfunction "IO18_30") (pintype "input+no_connect"))
    )
    (net (code "60") (name "unconnected-(U1-IO19-Pad31)") (class "Default")
      (node (ref "U1") (pin "31") (pinfunction "IO19_31") (pintype "input+no_connect"))
    )
    (net (code "61") (name "unconnected-(U1-IO21-Pad33)") (class "Default")
      (node (ref "U1") (pin "33") (pinfunction "IO21_33") (pintype "input+no_connect"))
    )
    (net (code "62") (name "unconnected-(U1-IO22-Pad36)") (class "Default")
      (node (ref "U1") (pin "36") (pinfunction "IO22_36") (pintype "input+no_connect"))
    )
    (net (code "63") (name "unconnected-(U1-IO23-Pad37)") (class "Default")
      (node (ref "U1") (pin "37") (pinfunction "IO23_37") (pintype "input+no_connect"))
    )
    (net (code "64") (name "unconnected-(U1-IO34-Pad6)") (class "Default")
      (node (ref "U1") (pin "6") (pinfunction "IO34_6") (pintype "input+no_connect"))
    )
    (net (code "65") (name "unconnected-(U1-IO35-Pad7)") (class "Default")
      (node (ref "U1") (pin "7") (pinfunction "IO35_7") (pintype "input+no_connect"))
    )
    (net (code "66") (name "unconnected-(U1-NC-Pad32)") (class "Default")
      (node (ref "U1") (pin "32") (pinfunction "NC_32") (pintype "input+no_connect"))
    )
    (net (code "67") (name "unconnected-(U1-SD2-Pad17)") (class "Default")
      (node (ref "U1") (pin "17") (pinfunction "SD2_17") (pintype "input+no_connect"))
    )
    (net (code "68") (name "unconnected-(U1-SD3-Pad18)") (class "Default")
      (node (ref "U1") (pin "18") (pinfunction "SD3_18") (pintype "input+no_connect"))
    )
    (net (code "69") (name "unconnected-(U1-SDI-Pad22)") (class "Default")
      (node (ref "U1") (pin "22") (pinfunction "SDI_22") (pintype "input+no_connect"))
    )
    (net (code "70") (name "unconnected-(U1-SDO-Pad21)") (class "Default")
      (node (ref "U1") (pin "21") (pinfunction "SDO_21") (pintype "input+no_connect"))
    )
    (net (code "71") (name "unconnected-(U1-SENSOR_VN-Pad5)") (class "Default")
      (node (ref "U1") (pin "5") (pinfunction "SENSOR_VN_5") (pintype "input+no_connect"))
    )
    (net (code "72") (name "unconnected-(U1-SENSOR_VP-Pad4)") (class "Default")
      (node (ref "U1") (pin "4") (pinfunction "SENSOR_VP_4") (pintype "input+no_connect"))
    )
    (net (code "73") (name "unconnected-(U6-RTS#-Pad4)") (class "Default")
      (node (ref "U6") (pin "4") (pinfunction "RTS#_4") (pintype "input+no_connect"))
    )
    (net (code "74") (name "unconnected-(USB1-ID-Pad4)") (class "Default")
      (node (ref "USB1") (pin "4") (pinfunction "ID_4") (pintype "input+no_connect"))
    )
  )
)
